# temperature_sensor.net
KiCad netlist of a schematic drawn in EAGLE
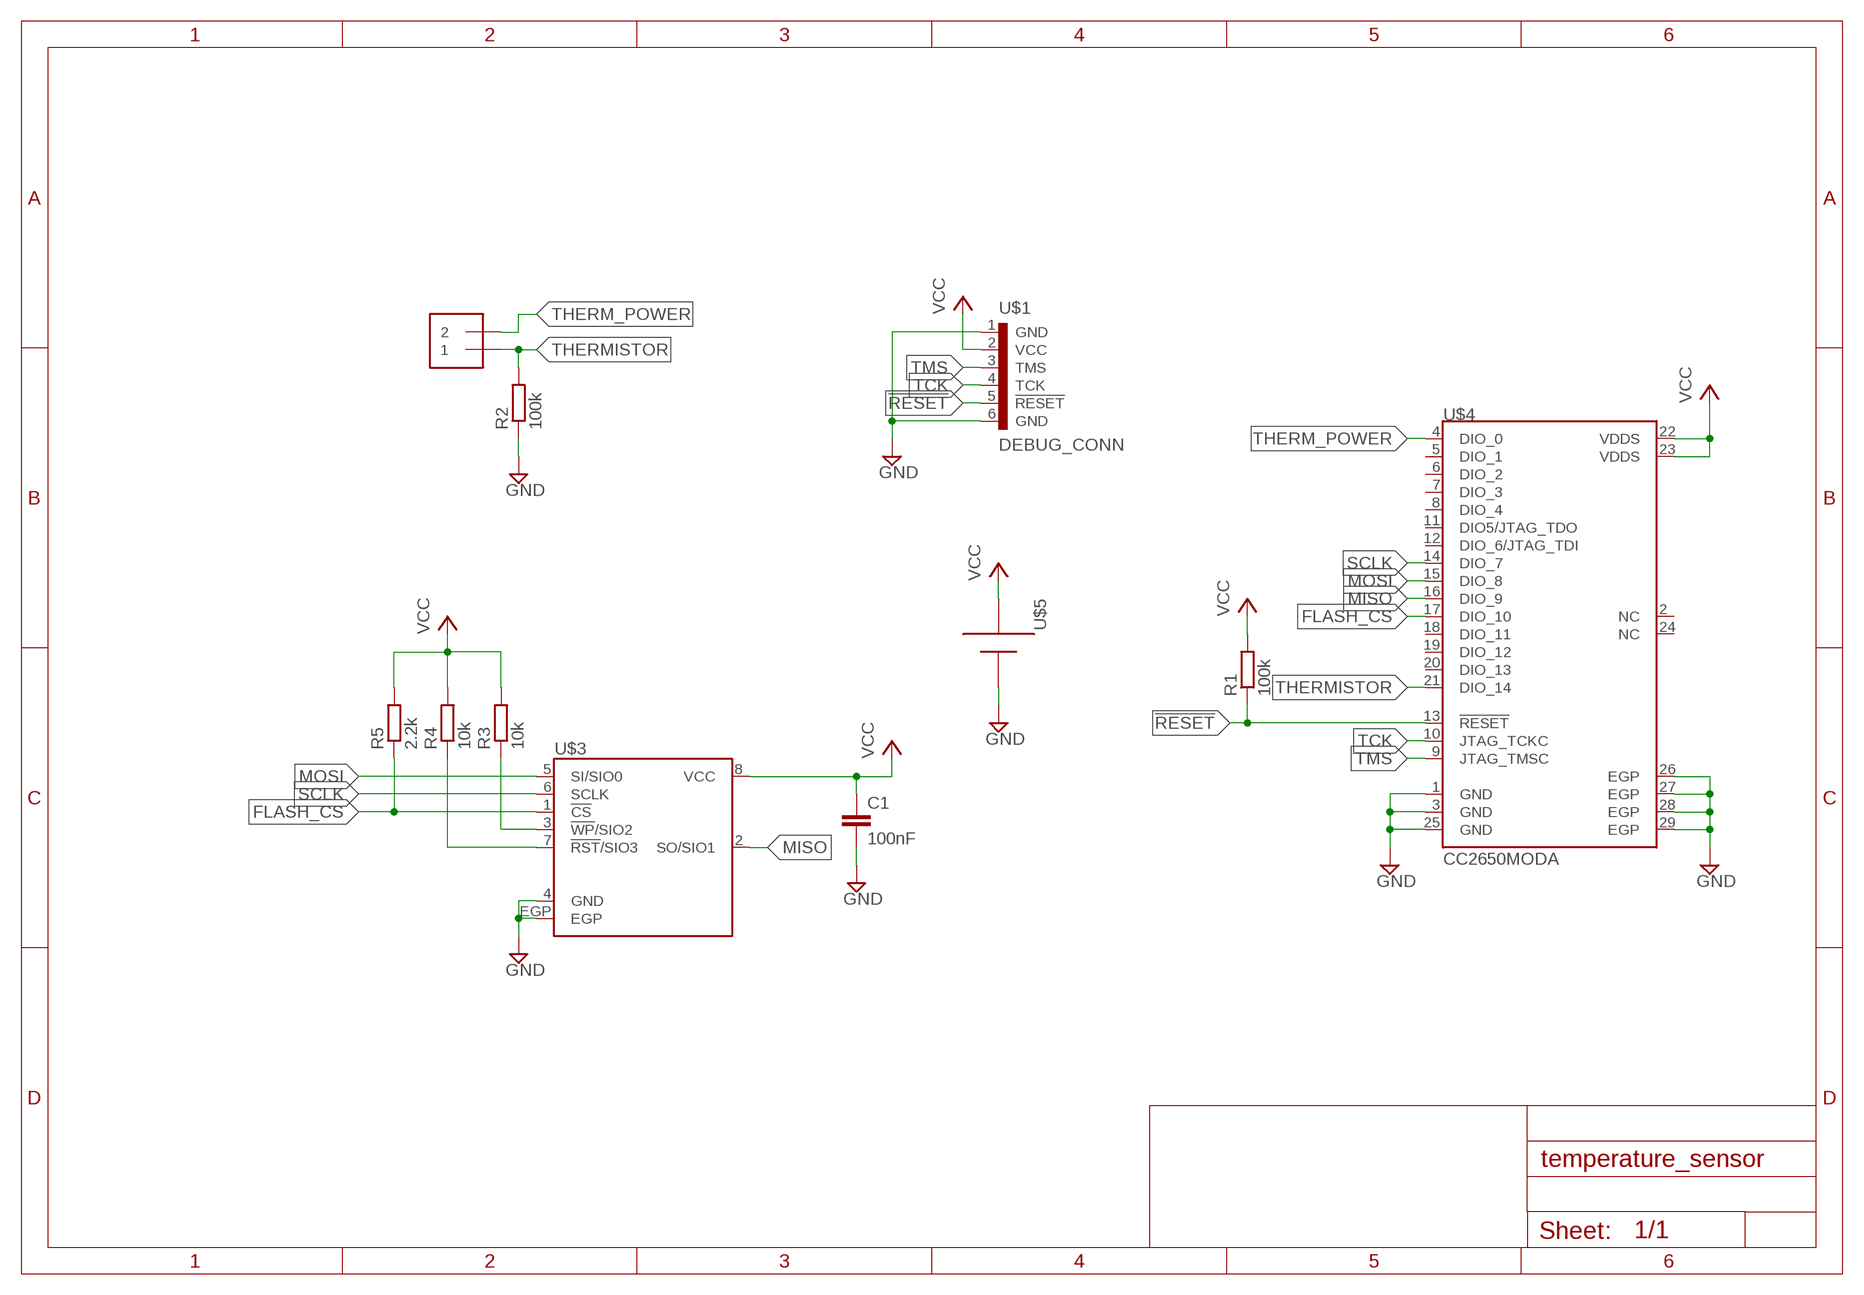
[diagram p0: schematic, sheet 1]

(export (version "E")
  (design (tool "Eeschema 10.0.6"))
  (components
    (comp (ref "C1")
      (value "100nF")
      (footprint "eagle-import:0402")
      (libsource (lib "eagle-import") (part "CAPACITOR_0402"))
    )
    (comp (ref "J2")
      (value "1X2-3.5MM")
      (footprint "eagle-import:1X2-3.5MM")
      (libsource (lib "eagle-import") (part "1X2-3.5MM"))
    )
    (comp (ref "R1")
      (value "100k")
      (footprint "eagle-import:0402")
      (libsource (lib "eagle-import") (part "RESISTOR_0402"))
    )
    (comp (ref "R2")
      (value "100k")
      (footprint "eagle-import:0402")
      (libsource (lib "eagle-import") (part "RESISTOR_0402"))
    )
    (comp (ref "R3")
      (value "10k")
      (footprint "eagle-import:0402")
      (libsource (lib "eagle-import") (part "RESISTOR_0402"))
    )
    (comp (ref "R4")
      (value "10k")
      (footprint "eagle-import:0402")
      (libsource (lib "eagle-import") (part "RESISTOR_0402"))
    )
    (comp (ref "R5")
      (value "2.2k")
      (footprint "eagle-import:0402")
      (libsource (lib "eagle-import") (part "RESISTOR_0402"))
    )
    (comp (ref "U$1")
      (value "DEBUG_CONN")
      (footprint "eagle-import:DEBUG_CONN")
      (libsource (lib "eagle-import") (part "DEBUG_CONN"))
    )
    (comp (ref "U$3")
      (value "MX25R8035FMX25R8035FZUIL0")
      (footprint "eagle-import:MX25R8035FZUIL0")
      (libsource (lib "eagle-import") (part "MX25R8035FMX25R8035FZUIL0"))
    )
    (comp (ref "U$4")
      (value "CC2650MODA")
      (footprint "eagle-import:CC2650MODA")
      (libsource (lib "eagle-import") (part "CC2650MODA"))
    )
    (comp (ref "U$5")
      (value "CR2_SPRINGS")
      (footprint "eagle-import:CR2")
      (libsource (lib "eagle-import") (part "CR2_SPRINGS"))
    )
  )
  (nets
    (net (code "1") (name "/~{RESET}") (class "Default")
      (node (ref "R1") (pin "1") (pinfunction "1_1") (pintype "passive"))
      (node (ref "U$1") (pin "5") (pinfunction "~{RESET}_5") (pintype "bidirectional"))
      (node (ref "U$4") (pin "13") (pinfunction "~{RESET}_13") (pintype "bidirectional"))
    )
    (net (code "2") (name "FLASH_CS") (class "Default")
      (node (ref "R5") (pin "1") (pinfunction "1_1") (pintype "passive"))
      (node (ref "U$3") (pin "1") (pinfunction "~{CS}_1") (pintype "input"))
      (node (ref "U$4") (pin "17") (pinfunction "DIO_10_17") (pintype "bidirectional"))
    )
    (net (code "3") (name "GND") (class "Default")
      (node (ref "C1") (pin "2") (pinfunction "2_2") (pintype "passive"))
      (node (ref "R2") (pin "1") (pinfunction "1_1") (pintype "passive"))
      (node (ref "U$1") (pin "1") (pinfunction "GND_1") (pintype "bidirectional"))
      (node (ref "U$1") (pin "6") (pinfunction "GND_6") (pintype "bidirectional"))
      (node (ref "U$3") (pin "4") (pinfunction "GND_4") (pintype "power_in"))
      (node (ref "U$3") (pin "EGP") (pinfunction "EGP_EGP") (pintype "power_in"))
      (node (ref "U$4") (pin "1") (pinfunction "GND_1") (pintype "power_in"))
      (node (ref "U$4") (pin "25") (pinfunction "GND_25") (pintype "power_in"))
      (node (ref "U$4") (pin "26") (pinfunction "EGP_26") (pintype "power_in"))
      (node (ref "U$4") (pin "27") (pinfunction "EGP_27") (pintype "power_in"))
      (node (ref "U$4") (pin "28") (pinfunction "EGP_28") (pintype "power_in"))
      (node (ref "U$4") (pin "29") (pinfunction "EGP_29") (pintype "power_in"))
      (node (ref "U$4") (pin "3") (pinfunction "GND_3") (pintype "power_in"))
      (node (ref "U$5") (pin "-") (pinfunction "-_-") (pintype "bidirectional"))
      (node (ref "U$5") (pin "-@1") (pinfunction "-_-@1") (pintype "bidirectional"))
      (node (ref "U$5") (pin "-@2") (pinfunction "-_-@2") (pintype "bidirectional"))
      (node (ref "U$5") (pin "-@3") (pinfunction "-_-@3") (pintype "bidirectional"))
    )
    (net (code "4") (name "MISO") (class "Default")
      (node (ref "U$3") (pin "2") (pinfunction "SO/SIO1_2") (pintype "bidirectional"))
      (node (ref "U$4") (pin "16") (pinfunction "DIO_9_16") (pintype "bidirectional"))
    )
    (net (code "5") (name "MOSI") (class "Default")
      (node (ref "U$3") (pin "5") (pinfunction "SI/SIO0_5") (pintype "bidirectional"))
      (node (ref "U$4") (pin "15") (pinfunction "DIO_8_15") (pintype "bidirectional"))
    )
    (net (code "6") (name "Net-(U$3-~{RST}{slash}SIO3)") (class "Default")
      (node (ref "R4") (pin "1") (pinfunction "1_1") (pintype "passive"))
      (node (ref "U$3") (pin "7") (pinfunction "~{RST}/SIO3_7") (pintype "bidirectional"))
    )
    (net (code "7") (name "Net-(U$3-~{WP}{slash}SIO2)") (class "Default")
      (node (ref "R3") (pin "1") (pinfunction "1_1") (pintype "passive"))
      (node (ref "U$3") (pin "3") (pinfunction "~{WP}/SIO2_3") (pintype "bidirectional"))
    )
    (net (code "8") (name "SCLK") (class "Default")
      (node (ref "U$3") (pin "6") (pinfunction "SCLK_6") (pintype "input"))
      (node (ref "U$4") (pin "14") (pinfunction "DIO_7_14") (pintype "bidirectional"))
    )
    (net (code "9") (name "TCK") (class "Default")
      (node (ref "U$1") (pin "4") (pinfunction "TCK_4") (pintype "bidirectional"))
      (node (ref "U$4") (pin "10") (pinfunction "JTAG_TCKC_10") (pintype "bidirectional"))
    )
    (net (code "10") (name "THERMISTOR") (class "Default")
      (node (ref "J2") (pin "1") (pinfunction "1_1") (pintype "passive"))
      (node (ref "R2") (pin "2") (pinfunction "2_2") (pintype "passive"))
      (node (ref "U$4") (pin "21") (pinfunction "DIO_14_21") (pintype "bidirectional"))
    )
    (net (code "11") (name "THERM_POWER") (class "Default")
      (node (ref "J2") (pin "2") (pinfunction "2_2") (pintype "passive"))
      (node (ref "U$4") (pin "4") (pinfunction "DIO_0_4") (pintype "bidirectional"))
    )
    (net (code "12") (name "TMS") (class "Default")
      (node (ref "U$1") (pin "3") (pinfunction "TMS_3") (pintype "bidirectional"))
      (node (ref "U$4") (pin "9") (pinfunction "JTAG_TMSC_9") (pintype "bidirectional"))
    )
    (net (code "13") (name "VCC") (class "Default")
      (node (ref "C1") (pin "1") (pinfunction "1_1") (pintype "passive"))
      (node (ref "R1") (pin "2") (pinfunction "2_2") (pintype "passive"))
      (node (ref "R3") (pin "2") (pinfunction "2_2") (pintype "passive"))
      (node (ref "R4") (pin "2") (pinfunction "2_2") (pintype "passive"))
      (node (ref "R5") (pin "2") (pinfunction "2_2") (pintype "passive"))
      (node (ref "U$1") (pin "2") (pinfunction "VCC_2") (pintype "bidirectional"))
      (node (ref "U$3") (pin "8") (pinfunction "VCC_8") (pintype "power_in"))
      (node (ref "U$4") (pin "22") (pinfunction "VDDS_22") (pintype "power_in"))
      (node (ref "U$4") (pin "23") (pinfunction "VDDS_23") (pintype "power_in"))
      (node (ref "U$5") (pin "+") (pinfunction "+_+") (pintype "bidirectional"))
      (node (ref "U$5") (pin "+@1") (pinfunction "+_+@1") (pintype "bidirectional"))
      (node (ref "U$5") (pin "+@2") (pinfunction "+_+@2") (pintype "bidirectional"))
      (node (ref "U$5") (pin "+@3") (pinfunction "+_+@3") (pintype "bidirectional"))
    )
    (net (code "14") (name "unconnected-(U$4-DIO5{slash}JTAG_TDO-Pad11)") (class "Default")
      (node (ref "U$4") (pin "11") (pinfunction "DIO5/JTAG_TDO_11") (pintype "bidirectional"))
    )
    (net (code "15") (name "unconnected-(U$4-DIO_1-Pad5)") (class "Default")
      (node (ref "U$4") (pin "5") (pinfunction "DIO_1_5") (pintype "bidirectional"))
    )
    (net (code "16") (name "unconnected-(U$4-DIO_2-Pad6)") (class "Default")
      (node (ref "U$4") (pin "6") (pinfunction "DIO_2_6") (pintype "bidirectional"))
    )
    (net (code "17") (name "unconnected-(U$4-DIO_3-Pad7)") (class "Default")
      (node (ref "U$4") (pin "7") (pinfunction "DIO_3_7") (pintype "bidirectional"))
    )
    (net (code "18") (name "unconnected-(U$4-DIO_4-Pad8)") (class "Default")
      (node (ref "U$4") (pin "8") (pinfunction "DIO_4_8") (pintype "bidirectional"))
    )
    (net (code "19") (name "unconnected-(U$4-DIO_6{slash}JTAG_TDI-Pad12)") (class "Default")
      (node (ref "U$4") (pin "12") (pinfunction "DIO_6/JTAG_TDI_12") (pintype "bidirectional"))
    )
    (net (code "20") (name "unconnected-(U$4-DIO_11-Pad18)") (class "Default")
      (node (ref "U$4") (pin "18") (pinfunction "DIO_11_18") (pintype "bidirectional"))
    )
    (net (code "21") (name "unconnected-(U$4-DIO_12-Pad19)") (class "Default")
      (node (ref "U$4") (pin "19") (pinfunction "DIO_12_19") (pintype "bidirectional"))
    )
    (net (code "22") (name "unconnected-(U$4-DIO_13-Pad20)") (class "Default")
      (node (ref "U$4") (pin "20") (pinfunction "DIO_13_20") (pintype "bidirectional"))
    )
    (net (code "23") (name "unconnected-(U$4-NC-Pad2)") (class "Default")
      (node (ref "U$4") (pin "2") (pinfunction "NC_2") (pintype "no_connect"))
    )
    (net (code "24") (name "unconnected-(U$4-NC-Pad24)") (class "Default")
      (node (ref "U$4") (pin "24") (pinfunction "NC_24") (pintype "no_connect"))
    )
  )
)
